# PAYL0008_GMSK_Prototyping_Board_no_proto.net
KiCad netlist of a schematic drawn in Altium Designer
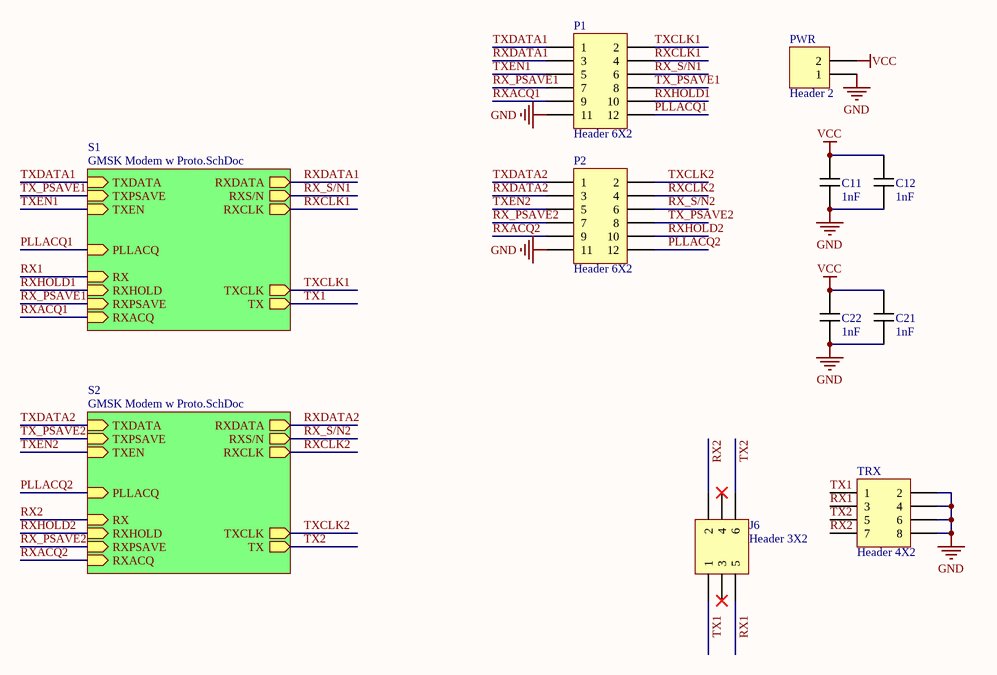
[diagram p0: PAYL0008 GMSK Prototyping Board no proto.SchDoc]

(export (version "E")
  (design (tool "Eeschema 10.0.6"))
  (components
    (comp (ref "C11")
      (value "1nF")
      (footprint "0805 Cap")
      (description "0805 MLCC - X7R, 10%")
      (fields (field (name "Comment") "0805 Cap"))
      (libsource (lib "GMSK Prototyping Board") (part "0805 MLCC - X7R, 10%"))
    )
    (comp (ref "C12")
      (value "1nF")
      (footprint "0805 Cap")
      (description "0805 MLCC - X7R, 10%")
      (fields (field (name "Comment") "0805 Cap"))
      (libsource (lib "GMSK Prototyping Board") (part "0805 MLCC - X7R, 10%"))
    )
    (comp (ref "C21")
      (value "1nF")
      (footprint "0805 Cap")
      (description "0805 MLCC - X7R, 10%")
      (fields (field (name "Comment") "0805 Cap"))
      (libsource (lib "GMSK Prototyping Board") (part "0805 MLCC - X7R, 10%"))
    )
    (comp (ref "C22")
      (value "1nF")
      (footprint "0805 Cap")
      (description "0805 MLCC - X7R, 10%")
      (fields (field (name "Comment") "0805 Cap"))
      (libsource (lib "GMSK Prototyping Board") (part "0805 MLCC - X7R, 10%"))
    )
    (comp (ref "J6")
      (value "Header 3X2")
      (footprint "HDR2X3")
      (description "Header, 3-Pin, Dual row")
      (fields (field (name "PUBLISHER") "Altium Limited"))
      (libsource (lib "GMSK Prototyping Board") (part "Header 3X2"))
    )
    (comp (ref "P1")
      (value "Header 6X2")
      (footprint "HDR2X6")
      (description "Header, 6-Pin, Dual row")
      (fields (field (name "PUBLISHER") "Altium Limited"))
      (libsource (lib "GMSK Prototyping Board") (part "Header 6X2"))
    )
    (comp (ref "P2")
      (value "Header 6X2")
      (footprint "HDR2X6")
      (description "Header, 6-Pin, Dual row")
      (fields (field (name "PUBLISHER") "Altium Limited"))
      (libsource (lib "GMSK Prototyping Board") (part "Header 6X2"))
    )
    (comp (ref "PWR")
      (value "Header 2")
      (footprint "HDR1X2")
      (description "Header, 2-Pin")
      (fields (field (name "PUBLISHER") "Altium Limited"))
      (libsource (lib "GMSK Prototyping Board") (part "Header 2"))
    )
    (comp (ref "TRX")
      (value "Header 4X2")
      (footprint "HDR2X4")
      (description "Header, 4-Pin, Dual row")
      (fields (field (name "PUBLISHER") "Altium Limited"))
      (libsource (lib "GMSK Prototyping Board") (part "Header 4X2"))
    )
  )
  (nets
    (net (code "1") (name "/PLLACQ1") (class "Default")
      (node (ref "P1") (pin "12") (pinfunction "12_12") (pintype "passive"))
    )
    (net (code "2") (name "/PLLACQ2") (class "Default")
      (node (ref "P2") (pin "12") (pinfunction "12_12") (pintype "passive"))
    )
    (net (code "3") (name "/RX1") (class "Default")
      (node (ref "J6") (pin "5") (pinfunction "5_5") (pintype "passive"))
      (node (ref "TRX") (pin "3") (pinfunction "3_3") (pintype "passive"))
    )
    (net (code "4") (name "/RX2") (class "Default")
      (node (ref "J6") (pin "2") (pinfunction "2_2") (pintype "passive"))
      (node (ref "TRX") (pin "7") (pinfunction "7_7") (pintype "passive"))
    )
    (net (code "5") (name "/RXACQ1") (class "Default")
      (node (ref "P1") (pin "9") (pinfunction "9_9") (pintype "passive"))
    )
    (net (code "6") (name "/RXACQ2") (class "Default")
      (node (ref "P2") (pin "9") (pinfunction "9_9") (pintype "passive"))
    )
    (net (code "7") (name "/RXCLK1") (class "Default")
      (node (ref "P1") (pin "4") (pinfunction "4_4") (pintype "passive"))
    )
    (net (code "8") (name "/RXCLK2") (class "Default")
      (node (ref "P2") (pin "4") (pinfunction "4_4") (pintype "passive"))
    )
    (net (code "9") (name "/RXDATA1") (class "Default")
      (node (ref "P1") (pin "3") (pinfunction "3_3") (pintype "passive"))
    )
    (net (code "10") (name "/RXDATA2") (class "Default")
      (node (ref "P2") (pin "3") (pinfunction "3_3") (pintype "passive"))
    )
    (net (code "11") (name "/RXHOLD1") (class "Default")
      (node (ref "P1") (pin "10") (pinfunction "10_10") (pintype "passive"))
    )
    (net (code "12") (name "/RXHOLD2") (class "Default")
      (node (ref "P2") (pin "10") (pinfunction "10_10") (pintype "passive"))
    )
    (net (code "13") (name "/RX_PSAVE1") (class "Default")
      (node (ref "P1") (pin "7") (pinfunction "7_7") (pintype "passive"))
    )
    (net (code "14") (name "/RX_PSAVE2") (class "Default")
      (node (ref "P2") (pin "7") (pinfunction "7_7") (pintype "passive"))
    )
    (net (code "15") (name "/RX_S{slash}N1") (class "Default")
      (node (ref "P1") (pin "6") (pinfunction "6_6") (pintype "passive"))
    )
    (net (code "16") (name "/RX_S{slash}N2") (class "Default")
      (node (ref "P2") (pin "6") (pinfunction "6_6") (pintype "passive"))
    )
    (net (code "17") (name "/TX1") (class "Default")
      (node (ref "J6") (pin "1") (pinfunction "1_1") (pintype "passive"))
      (node (ref "TRX") (pin "1") (pinfunction "1_1") (pintype "passive"))
    )
    (net (code "18") (name "/TX2") (class "Default")
      (node (ref "J6") (pin "6") (pinfunction "6_6") (pintype "passive"))
      (node (ref "TRX") (pin "5") (pinfunction "5_5") (pintype "passive"))
    )
    (net (code "19") (name "/TXCLK1") (class "Default")
      (node (ref "P1") (pin "2") (pinfunction "2_2") (pintype "passive"))
    )
    (net (code "20") (name "/TXCLK2") (class "Default")
      (node (ref "P2") (pin "2") (pinfunction "2_2") (pintype "passive"))
    )
    (net (code "21") (name "/TXDATA1") (class "Default")
      (node (ref "P1") (pin "1") (pinfunction "1_1") (pintype "passive"))
    )
    (net (code "22") (name "/TXDATA2") (class "Default")
      (node (ref "P2") (pin "1") (pinfunction "1_1") (pintype "passive"))
    )
    (net (code "23") (name "/TXEN1") (class "Default")
      (node (ref "P1") (pin "5") (pinfunction "5_5") (pintype "passive"))
    )
    (net (code "24") (name "/TXEN2") (class "Default")
      (node (ref "P2") (pin "5") (pinfunction "5_5") (pintype "passive"))
    )
    (net (code "25") (name "/TX_PSAVE1") (class "Default")
      (node (ref "P1") (pin "8") (pinfunction "8_8") (pintype "passive"))
    )
    (net (code "26") (name "/TX_PSAVE2") (class "Default")
      (node (ref "P2") (pin "8") (pinfunction "8_8") (pintype "passive"))
    )
    (net (code "27") (name "GND") (class "Default")
      (node (ref "C11") (pin "2") (pinfunction "2_2") (pintype "passive"))
      (node (ref "C12") (pin "2") (pinfunction "2_2") (pintype "passive"))
      (node (ref "C21") (pin "1") (pinfunction "1_1") (pintype "passive"))
      (node (ref "C22") (pin "1") (pinfunction "1_1") (pintype "passive"))
      (node (ref "P1") (pin "11") (pinfunction "11_11") (pintype "passive"))
      (node (ref "P2") (pin "11") (pinfunction "11_11") (pintype "passive"))
      (node (ref "PWR") (pin "1") (pinfunction "1_1") (pintype "passive"))
      (node (ref "TRX") (pin "2") (pinfunction "2_2") (pintype "passive"))
      (node (ref "TRX") (pin "4") (pinfunction "4_4") (pintype "passive"))
      (node (ref "TRX") (pin "6") (pinfunction "6_6") (pintype "passive"))
      (node (ref "TRX") (pin "8") (pinfunction "8_8") (pintype "passive"))
    )
    (net (code "28") (name "VCC") (class "Default")
      (node (ref "C11") (pin "1") (pinfunction "1_1") (pintype "passive"))
      (node (ref "C12") (pin "1") (pinfunction "1_1") (pintype "passive"))
      (node (ref "C21") (pin "2") (pinfunction "2_2") (pintype "passive"))
      (node (ref "C22") (pin "2") (pinfunction "2_2") (pintype "passive"))
      (node (ref "PWR") (pin "2") (pinfunction "2_2") (pintype "passive"))
    )
    (net (code "29") (name "unconnected-(J6-Pad3)") (class "Default")
      (node (ref "J6") (pin "3") (pinfunction "3_3") (pintype "passive+no_connect"))
    )
    (net (code "30") (name "unconnected-(J6-Pad4)") (class "Default")
      (node (ref "J6") (pin "4") (pinfunction "4_4") (pintype "passive+no_connect"))
    )
  )
)
